# Qwiic_PIR.net
KiCad netlist of a schematic drawn in EAGLE
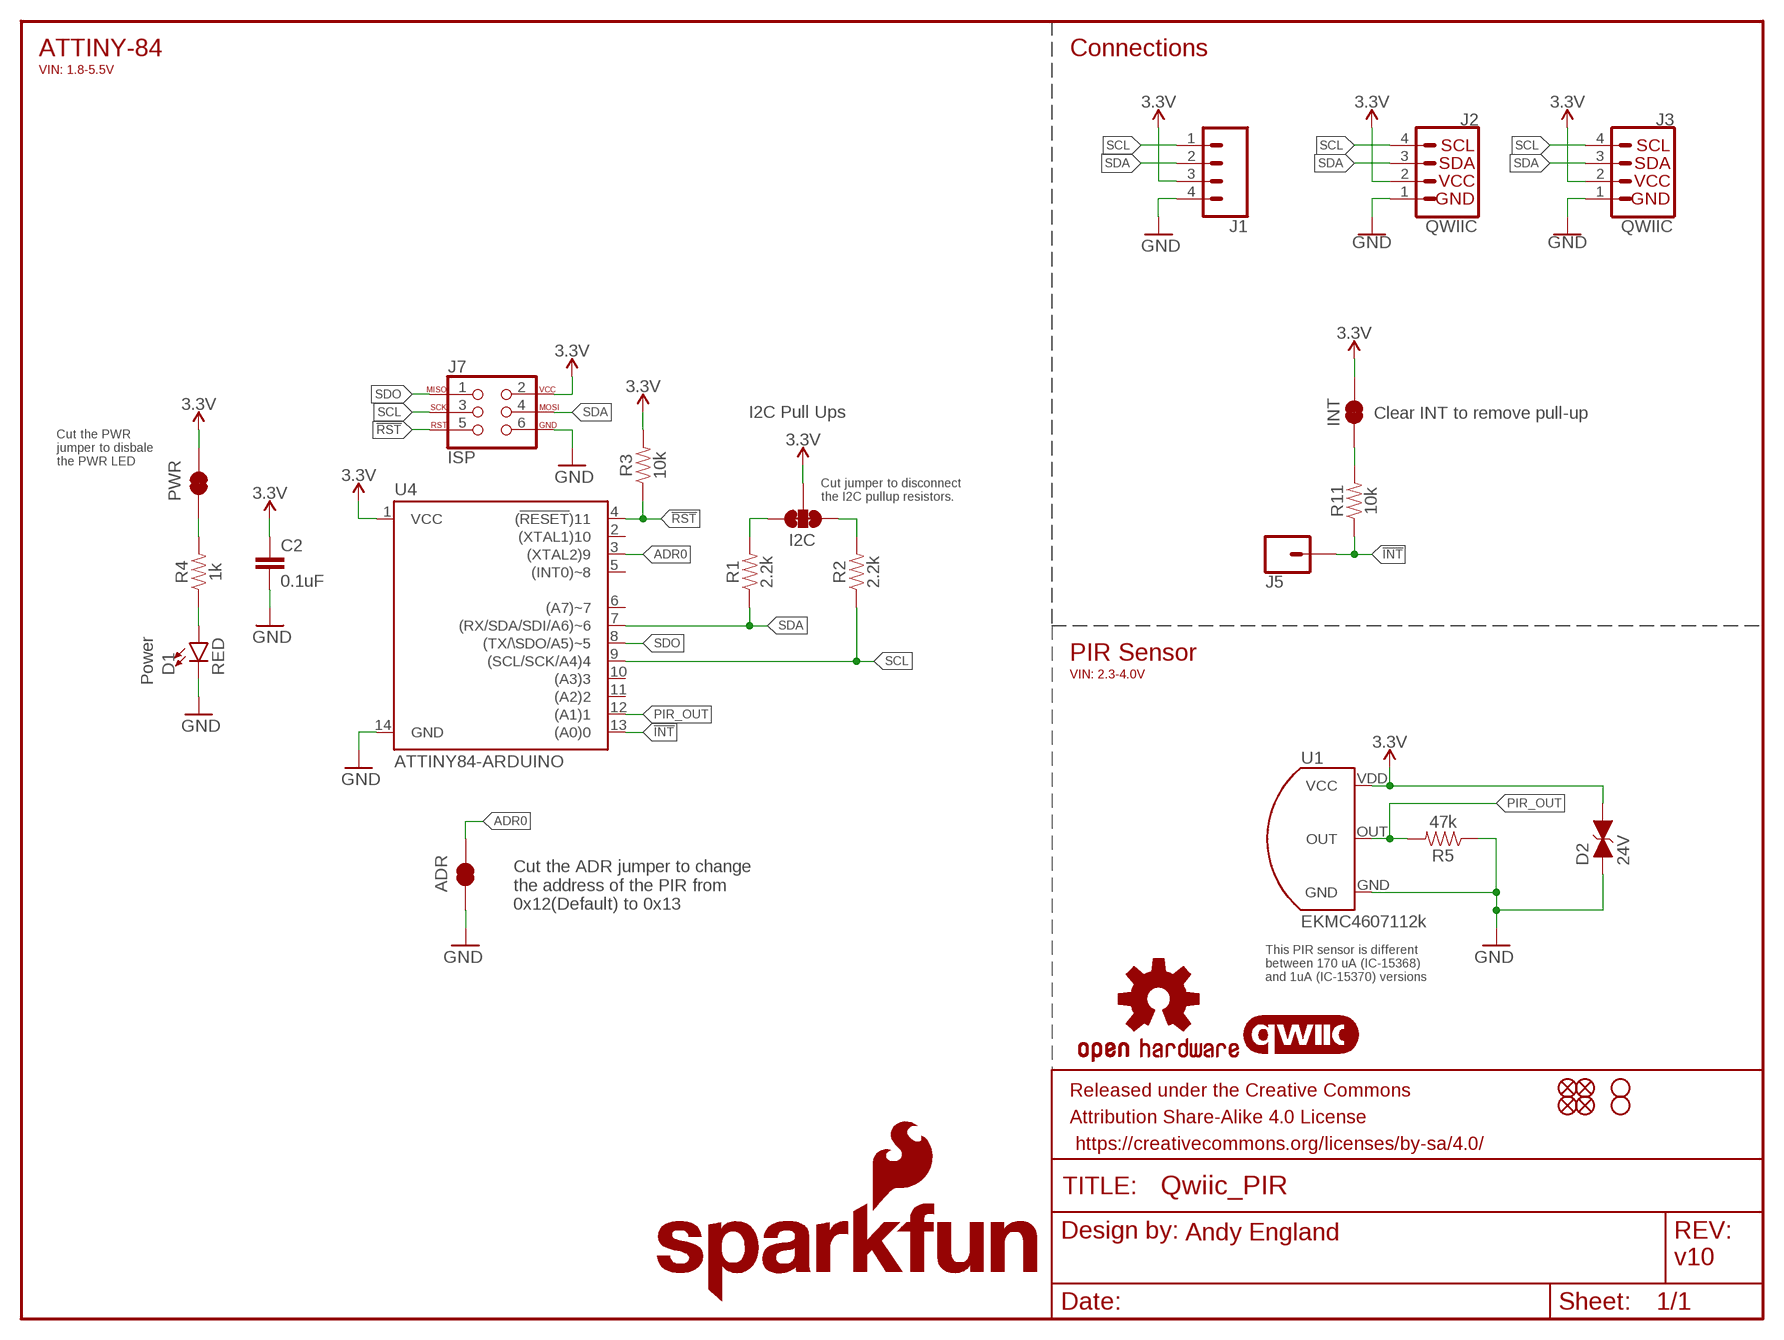
[diagram p0: schematic, sheet 1]

(export (version "E")
  (design (tool "Eeschema 10.0.6"))
  (components
    (comp (ref "ADR")
      (value "JUMPER-SMT_2_NC_TRACE_SILK")
      (footprint "eagle-import:SMT-JUMPER_2_NC_TRACE_SILK")
      (libsource (lib "eagle-import") (part "JUMPER-SMT_2_NC_TRACE_SILK"))
    )
    (comp (ref "C2")
      (value "0.1uF")
      (footprint "eagle-import:0603")
      (libsource (lib "eagle-import") (part "0.1UF-0603-25V-(+80/-20%)"))
    )
    (comp (ref "D1")
      (value "RED")
      (footprint "eagle-import:LED-0603")
      (libsource (lib "eagle-import") (part "LED-RED0603"))
    )
    (comp (ref "D2")
      (value "24V")
      (footprint "eagle-import:0603")
      (libsource (lib "eagle-import") (part "DIODE_TVS"))
    )
    (comp (ref "FRAME1")
      (value "FRAME-LETTER")
      (footprint "eagle-import:CREATIVE_COMMONS")
      (libsource (lib "eagle-import") (part "FRAME-LETTER"))
    )
    (comp (ref "H1")
      (value "STAND-OFF")
      (footprint "eagle-import:STAND-OFF")
      (libsource (lib "eagle-import") (part "STAND-OFF"))
    )
    (comp (ref "H2")
      (value "STAND-OFF")
      (footprint "eagle-import:STAND-OFF")
      (libsource (lib "eagle-import") (part "STAND-OFF"))
    )
    (comp (ref "I2C")
      (value "JUMPER-SMT_3_2-NC_TRACE_SILK")
      (footprint "eagle-import:SMT-JUMPER_3_2-NC_TRACE_SILK")
      (libsource (lib "eagle-import") (part "JUMPER-SMT_3_2-NC_TRACE_SILK"))
    )
    (comp (ref "INT")
      (value "JUMPER-SMT_2_NC_TRACE_SILK")
      (footprint "eagle-import:SMT-JUMPER_2_NC_TRACE_SILK")
      (libsource (lib "eagle-import") (part "JUMPER-SMT_2_NC_TRACE_SILK"))
    )
    (comp (ref "J1")
      (value "CONN_041X04_NO_SILK")
      (footprint "eagle-import:1X04_NO_SILK")
      (libsource (lib "eagle-import") (part "CONN_041X04_NO_SILK"))
    )
    (comp (ref "J2")
      (value "QWIIC")
      (footprint "eagle-import:JST04_1MM_RA")
      (libsource (lib "eagle-import") (part "QWIIC_CONNECTORJS-1MM"))
    )
    (comp (ref "J3")
      (value "QWIIC")
      (footprint "eagle-import:JST04_1MM_RA")
      (libsource (lib "eagle-import") (part "QWIIC_CONNECTORJS-1MM"))
    )
    (comp (ref "J5")
      (value "CONN_01PTH_NO_SILK_YES_STOP")
      (footprint "eagle-import:1X01_NO_SILK")
      (libsource (lib "eagle-import") (part "CONN_01PTH_NO_SILK_YES_STOP"))
    )
    (comp (ref "J7")
      (value "ISP")
      (footprint "eagle-import:2X3_TEST_POINTS")
      (libsource (lib "eagle-import") (part "AVR_SPI_PROG_3X2TESTPOINTS"))
    )
    (comp (ref "JP2")
      (value "FIDUCIALUFIDUCIAL")
      (footprint "eagle-import:MICRO-FIDUCIAL")
      (libsource (lib "eagle-import") (part "FIDUCIALUFIDUCIAL"))
    )
    (comp (ref "JP6")
      (value "FIDUCIALUFIDUCIAL")
      (footprint "eagle-import:MICRO-FIDUCIAL")
      (libsource (lib "eagle-import") (part "FIDUCIALUFIDUCIAL"))
    )
    (comp (ref "JP8")
      (value "FIDUCIALUFIDUCIAL")
      (footprint "eagle-import:MICRO-FIDUCIAL")
      (libsource (lib "eagle-import") (part "FIDUCIALUFIDUCIAL"))
    )
    (comp (ref "JP9")
      (value "FIDUCIALUFIDUCIAL")
      (footprint "eagle-import:MICRO-FIDUCIAL")
      (libsource (lib "eagle-import") (part "FIDUCIALUFIDUCIAL"))
    )
    (comp (ref "LOGO1")
      (value "OSHW-LOGOMINI")
      (footprint "eagle-import:OSHW-LOGO-MINI")
      (libsource (lib "eagle-import") (part "OSHW-LOGOMINI"))
    )
    (comp (ref "LOGO2")
      (value "QWIIC_LOGO_5MM")
      (footprint "eagle-import:QWIIC_5MM")
      (libsource (lib "eagle-import") (part "QWIIC_LOGO_5MM"))
    )
    (comp (ref "LOGO3")
      (value "SFE_LOGO_NAME.1_INCH")
      (footprint "eagle-import:SFE_LOGO_NAME_.1")
      (libsource (lib "eagle-import") (part "SFE_LOGO_NAME.1_INCH"))
    )
    (comp (ref "LOGO4")
      (value "SFE_LOGO_FLAME.1_INCH")
      (footprint "eagle-import:SFE_LOGO_FLAME_.1")
      (libsource (lib "eagle-import") (part "SFE_LOGO_FLAME.1_INCH"))
    )
    (comp (ref "PWR")
      (value "JUMPER-SMT_2_NC_TRACE_SILK")
      (footprint "eagle-import:SMT-JUMPER_2_NC_TRACE_SILK")
      (libsource (lib "eagle-import") (part "JUMPER-SMT_2_NC_TRACE_SILK"))
    )
    (comp (ref "R1")
      (value "2.2k")
      (footprint "eagle-import:0603")
      (libsource (lib "eagle-import") (part "2.2KOHM-0603-1/10W-1%"))
    )
    (comp (ref "R2")
      (value "2.2k")
      (footprint "eagle-import:0603")
      (libsource (lib "eagle-import") (part "2.2KOHM-0603-1/10W-1%"))
    )
    (comp (ref "R3")
      (value "10k")
      (footprint "eagle-import:0603")
      (libsource (lib "eagle-import") (part "10KOHM-0603-1/10W-1%"))
    )
    (comp (ref "R4")
      (value "1k")
      (footprint "eagle-import:0603")
      (libsource (lib "eagle-import") (part "1KOHM-0603-1/10W-1%"))
    )
    (comp (ref "R5")
      (value "47k")
      (footprint "eagle-import:0603")
      (libsource (lib "eagle-import") (part "47KOHM-0603-1/10W-1%"))
    )
    (comp (ref "R11")
      (value "10k")
      (footprint "eagle-import:0603")
      (libsource (lib "eagle-import") (part "10KOHM-0603-1/10W-1%"))
    )
    (comp (ref "U1")
      (value "EKMC4607112k")
      (footprint "eagle-import:TO-3")
      (libsource (lib "eagle-import") (part "PIR_EKM4607112K"))
    )
    (comp (ref "U4")
      (value "ATTINY84-ARDUINO")
      (footprint "eagle-import:SO14")
      (libsource (lib "eagle-import") (part "ATTINY84-ARDUINO"))
    )
  )
  (nets
    (net (code "1") (name "/~{INT}") (class "Default")
      (node (ref "J5") (pin "1") (pinfunction "1_1") (pintype "passive"))
      (node (ref "R11") (pin "1") (pinfunction "1_1") (pintype "passive"))
      (node (ref "U4") (pin "13") (pinfunction "(A0)0_13") (pintype "bidirectional"))
    )
    (net (code "2") (name "/~{RST}") (class "Default")
      (node (ref "J7") (pin "5") (pinfunction "5_5") (pintype "passive"))
      (node (ref "R3") (pin "1") (pinfunction "1_1") (pintype "passive"))
      (node (ref "U4") (pin "4") (pinfunction "(~{RESET})11_4") (pintype "bidirectional"))
    )
    (net (code "3") (name "3.3V") (class "Default")
      (node (ref "C2") (pin "1") (pinfunction "1_1") (pintype "passive"))
      (node (ref "D2") (pin "2") (pinfunction "C_2") (pintype "passive"))
      (node (ref "I2C") (pin "2") (pinfunction "2_2") (pintype "passive"))
      (node (ref "INT") (pin "2") (pinfunction "2_2") (pintype "passive"))
      (node (ref "J1") (pin "3") (pinfunction "3_3") (pintype "passive"))
      (node (ref "J2") (pin "2") (pinfunction "2_2") (pintype "power_in"))
      (node (ref "J3") (pin "2") (pinfunction "2_2") (pintype "power_in"))
      (node (ref "J7") (pin "2") (pinfunction "2_2") (pintype "passive"))
      (node (ref "PWR") (pin "2") (pinfunction "2_2") (pintype "passive"))
      (node (ref "R3") (pin "2") (pinfunction "2_2") (pintype "passive"))
      (node (ref "U1") (pin "VDD") (pinfunction "VCC_VDD") (pintype "bidirectional"))
      (node (ref "U4") (pin "1") (pinfunction "VCC_1") (pintype "bidirectional"))
    )
    (net (code "4") (name "ADR0") (class "Default")
      (node (ref "ADR") (pin "2") (pinfunction "2_2") (pintype "passive"))
      (node (ref "U4") (pin "3") (pinfunction "(XTAL2)9_3") (pintype "bidirectional"))
    )
    (net (code "5") (name "GND") (class "Default")
      (node (ref "ADR") (pin "1") (pinfunction "1_1") (pintype "passive"))
      (node (ref "C2") (pin "2") (pinfunction "2_2") (pintype "passive"))
      (node (ref "D1") (pin "C") (pinfunction "C_C") (pintype "passive"))
      (node (ref "D2") (pin "1") (pinfunction "A_1") (pintype "passive"))
      (node (ref "J1") (pin "4") (pinfunction "4_4") (pintype "passive"))
      (node (ref "J2") (pin "1") (pinfunction "1_1") (pintype "power_in"))
      (node (ref "J3") (pin "1") (pinfunction "1_1") (pintype "power_in"))
      (node (ref "J7") (pin "6") (pinfunction "6_6") (pintype "passive"))
      (node (ref "R5") (pin "1") (pinfunction "1_1") (pintype "passive"))
      (node (ref "U1") (pin "GND") (pinfunction "GND_GND") (pintype "bidirectional"))
      (node (ref "U4") (pin "14") (pinfunction "GND_14") (pintype "bidirectional"))
    )
    (net (code "6") (name "Net-(D1-PadA)") (class "Default")
      (node (ref "D1") (pin "A") (pinfunction "A_A") (pintype "passive"))
      (node (ref "R4") (pin "1") (pinfunction "1_1") (pintype "passive"))
    )
    (net (code "7") (name "Net-(I2C-Pad1)") (class "Default")
      (node (ref "I2C") (pin "1") (pinfunction "1_1") (pintype "passive"))
      (node (ref "R2") (pin "2") (pinfunction "2_2") (pintype "passive"))
    )
    (net (code "8") (name "Net-(I2C-Pad3)") (class "Default")
      (node (ref "I2C") (pin "3") (pinfunction "3_3") (pintype "passive"))
      (node (ref "R1") (pin "2") (pinfunction "2_2") (pintype "passive"))
    )
    (net (code "9") (name "Net-(INT-Pad1)") (class "Default")
      (node (ref "INT") (pin "1") (pinfunction "1_1") (pintype "passive"))
      (node (ref "R11") (pin "2") (pinfunction "2_2") (pintype "passive"))
    )
    (net (code "10") (name "Net-(PWR-Pad1)") (class "Default")
      (node (ref "PWR") (pin "1") (pinfunction "1_1") (pintype "passive"))
      (node (ref "R4") (pin "2") (pinfunction "2_2") (pintype "passive"))
    )
    (net (code "11") (name "PIR_OUT") (class "Default")
      (node (ref "R5") (pin "2") (pinfunction "2_2") (pintype "passive"))
      (node (ref "U1") (pin "OUT") (pinfunction "OUT_OUT") (pintype "bidirectional"))
      (node (ref "U4") (pin "12") (pinfunction "(A1)1_12") (pintype "bidirectional"))
    )
    (net (code "12") (name "SCL") (class "Default")
      (node (ref "J1") (pin "1") (pinfunction "1_1") (pintype "passive"))
      (node (ref "J2") (pin "4") (pinfunction "4_4") (pintype "passive"))
      (node (ref "J3") (pin "4") (pinfunction "4_4") (pintype "passive"))
      (node (ref "J7") (pin "3") (pinfunction "3_3") (pintype "passive"))
      (node (ref "R2") (pin "1") (pinfunction "1_1") (pintype "passive"))
      (node (ref "U4") (pin "9") (pinfunction "(SCL/SCK/A4)4_9") (pintype "bidirectional"))
    )
    (net (code "13") (name "SDA") (class "Default")
      (node (ref "J1") (pin "2") (pinfunction "2_2") (pintype "passive"))
      (node (ref "J2") (pin "3") (pinfunction "3_3") (pintype "passive"))
      (node (ref "J3") (pin "3") (pinfunction "3_3") (pintype "passive"))
      (node (ref "J7") (pin "4") (pinfunction "4_4") (pintype "passive"))
      (node (ref "R1") (pin "1") (pinfunction "1_1") (pintype "passive"))
      (node (ref "U4") (pin "7") (pinfunction "(RX/SDA/SDI/A6)~{6}_7") (pintype "bidirectional"))
    )
    (net (code "14") (name "SDO") (class "Default")
      (node (ref "J7") (pin "1") (pinfunction "1_1") (pintype "passive"))
      (node (ref "U4") (pin "8") (pinfunction "(TX/\\SDO/A5)~{5}_8") (pintype "bidirectional"))
    )
    (net (code "15") (name "unconnected-(U4-(A2)2-Pad11)") (class "Default")
      (node (ref "U4") (pin "11") (pinfunction "(A2)2_11") (pintype "bidirectional"))
    )
    (net (code "16") (name "unconnected-(U4-(A3)3-Pad10)") (class "Default")
      (node (ref "U4") (pin "10") (pinfunction "(A3)3_10") (pintype "bidirectional"))
    )
    (net (code "17") (name "unconnected-(U4-(A7)~{7}-Pad6)") (class "Default")
      (node (ref "U4") (pin "6") (pinfunction "(A7)~{7}_6") (pintype "bidirectional"))
    )
    (net (code "18") (name "unconnected-(U4-(INT0)~{8}-Pad5)") (class "Default")
      (node (ref "U4") (pin "5") (pinfunction "(INT0)~{8}_5") (pintype "bidirectional"))
    )
    (net (code "19") (name "unconnected-(U4-(XTAL1)10-Pad2)") (class "Default")
      (node (ref "U4") (pin "2") (pinfunction "(XTAL1)10_2") (pintype "bidirectional"))
    )
  )
)
